# CurrentMonitor2.net
KiCad netlist of a schematic drawn in EAGLE
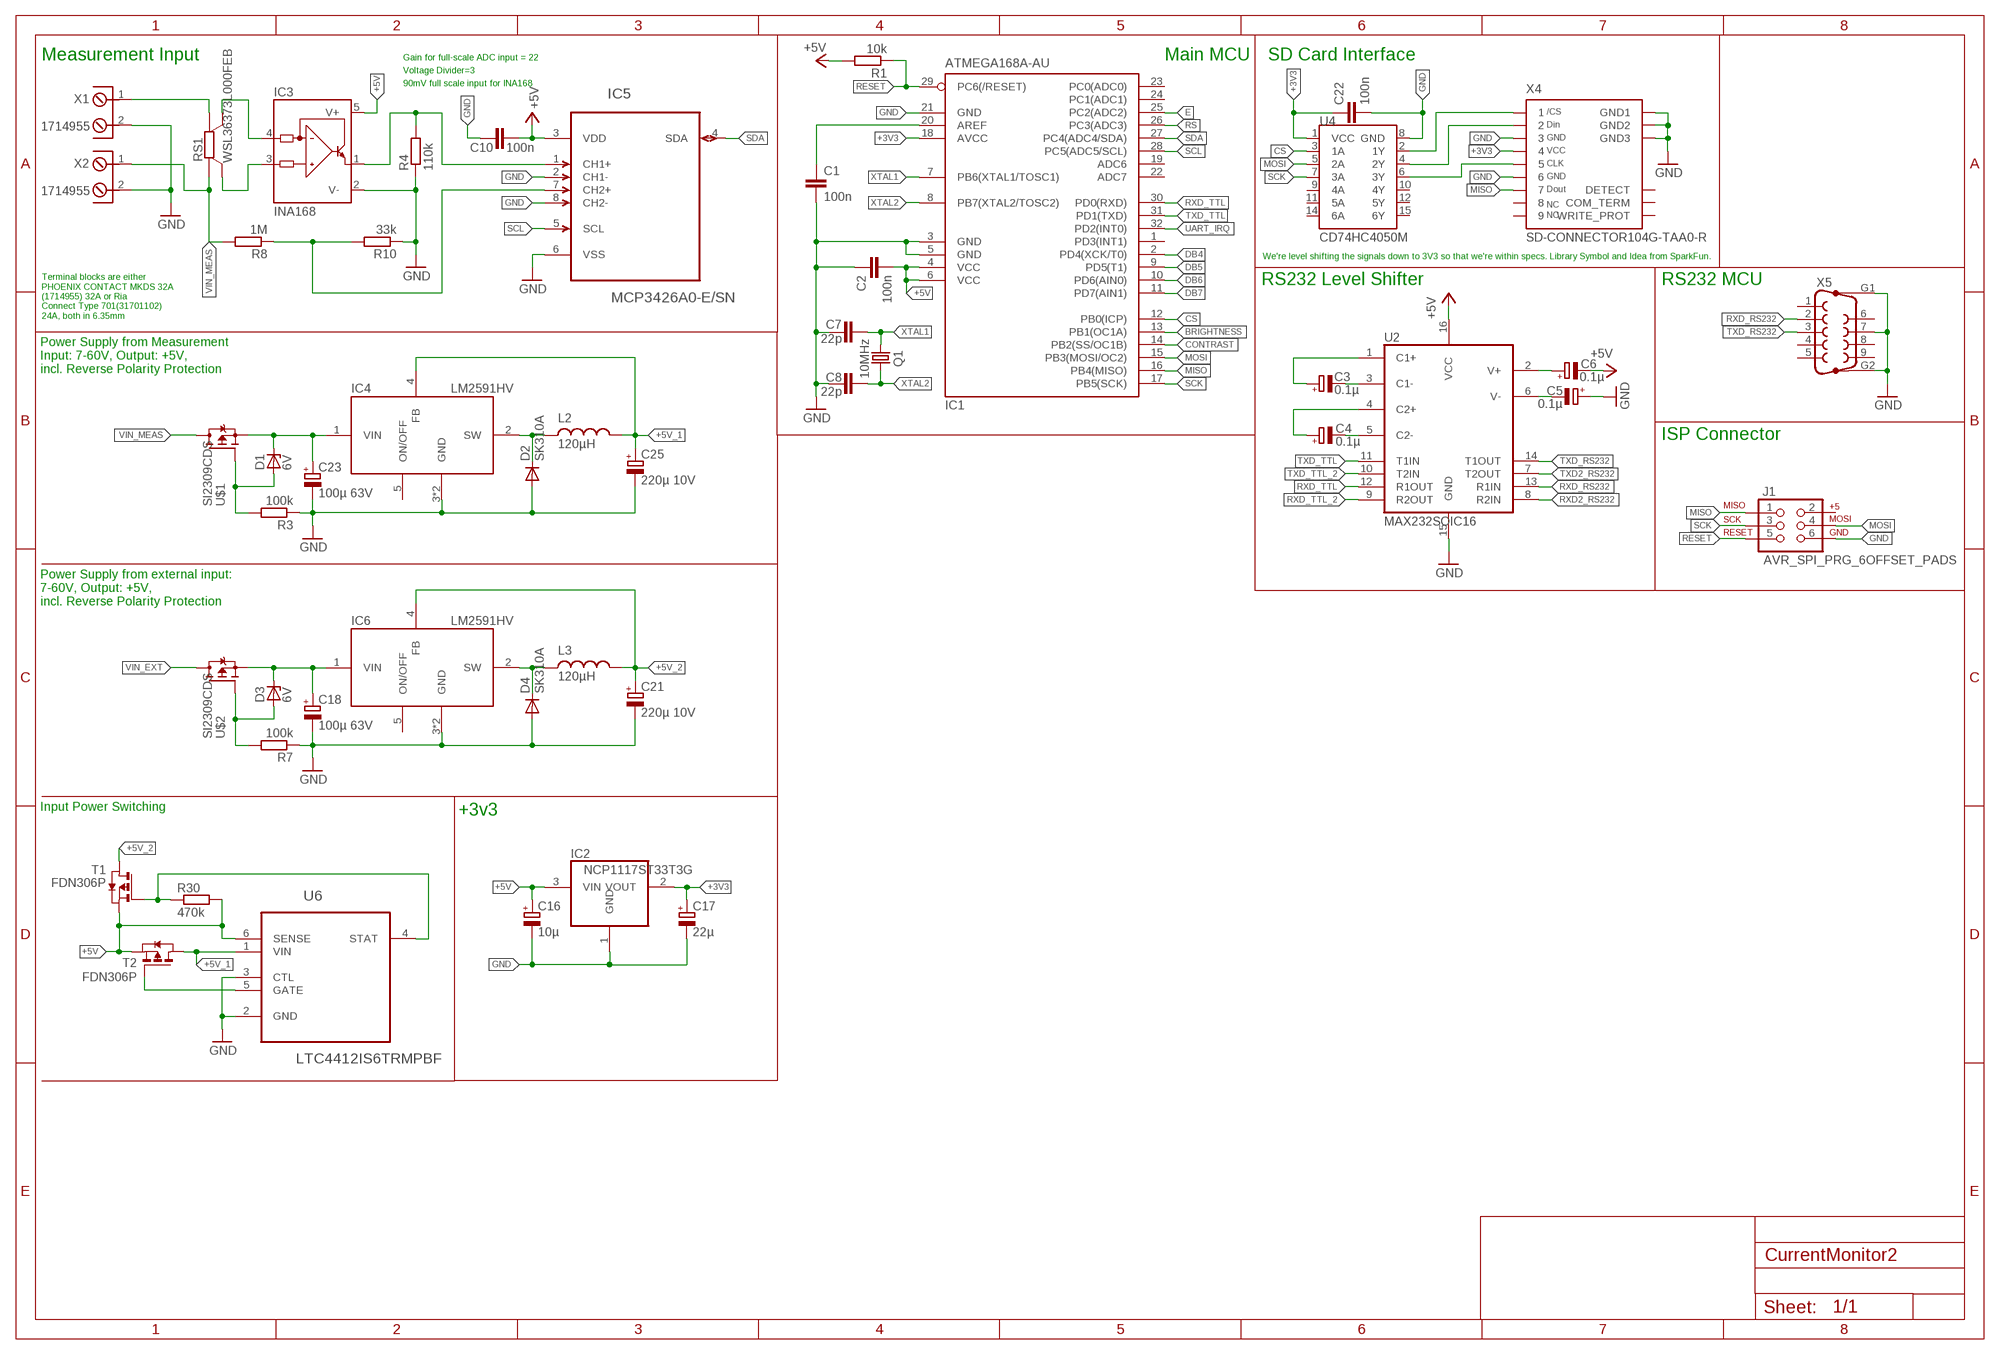
[diagram p0: schematic, sheet 1, part 1 of 2]
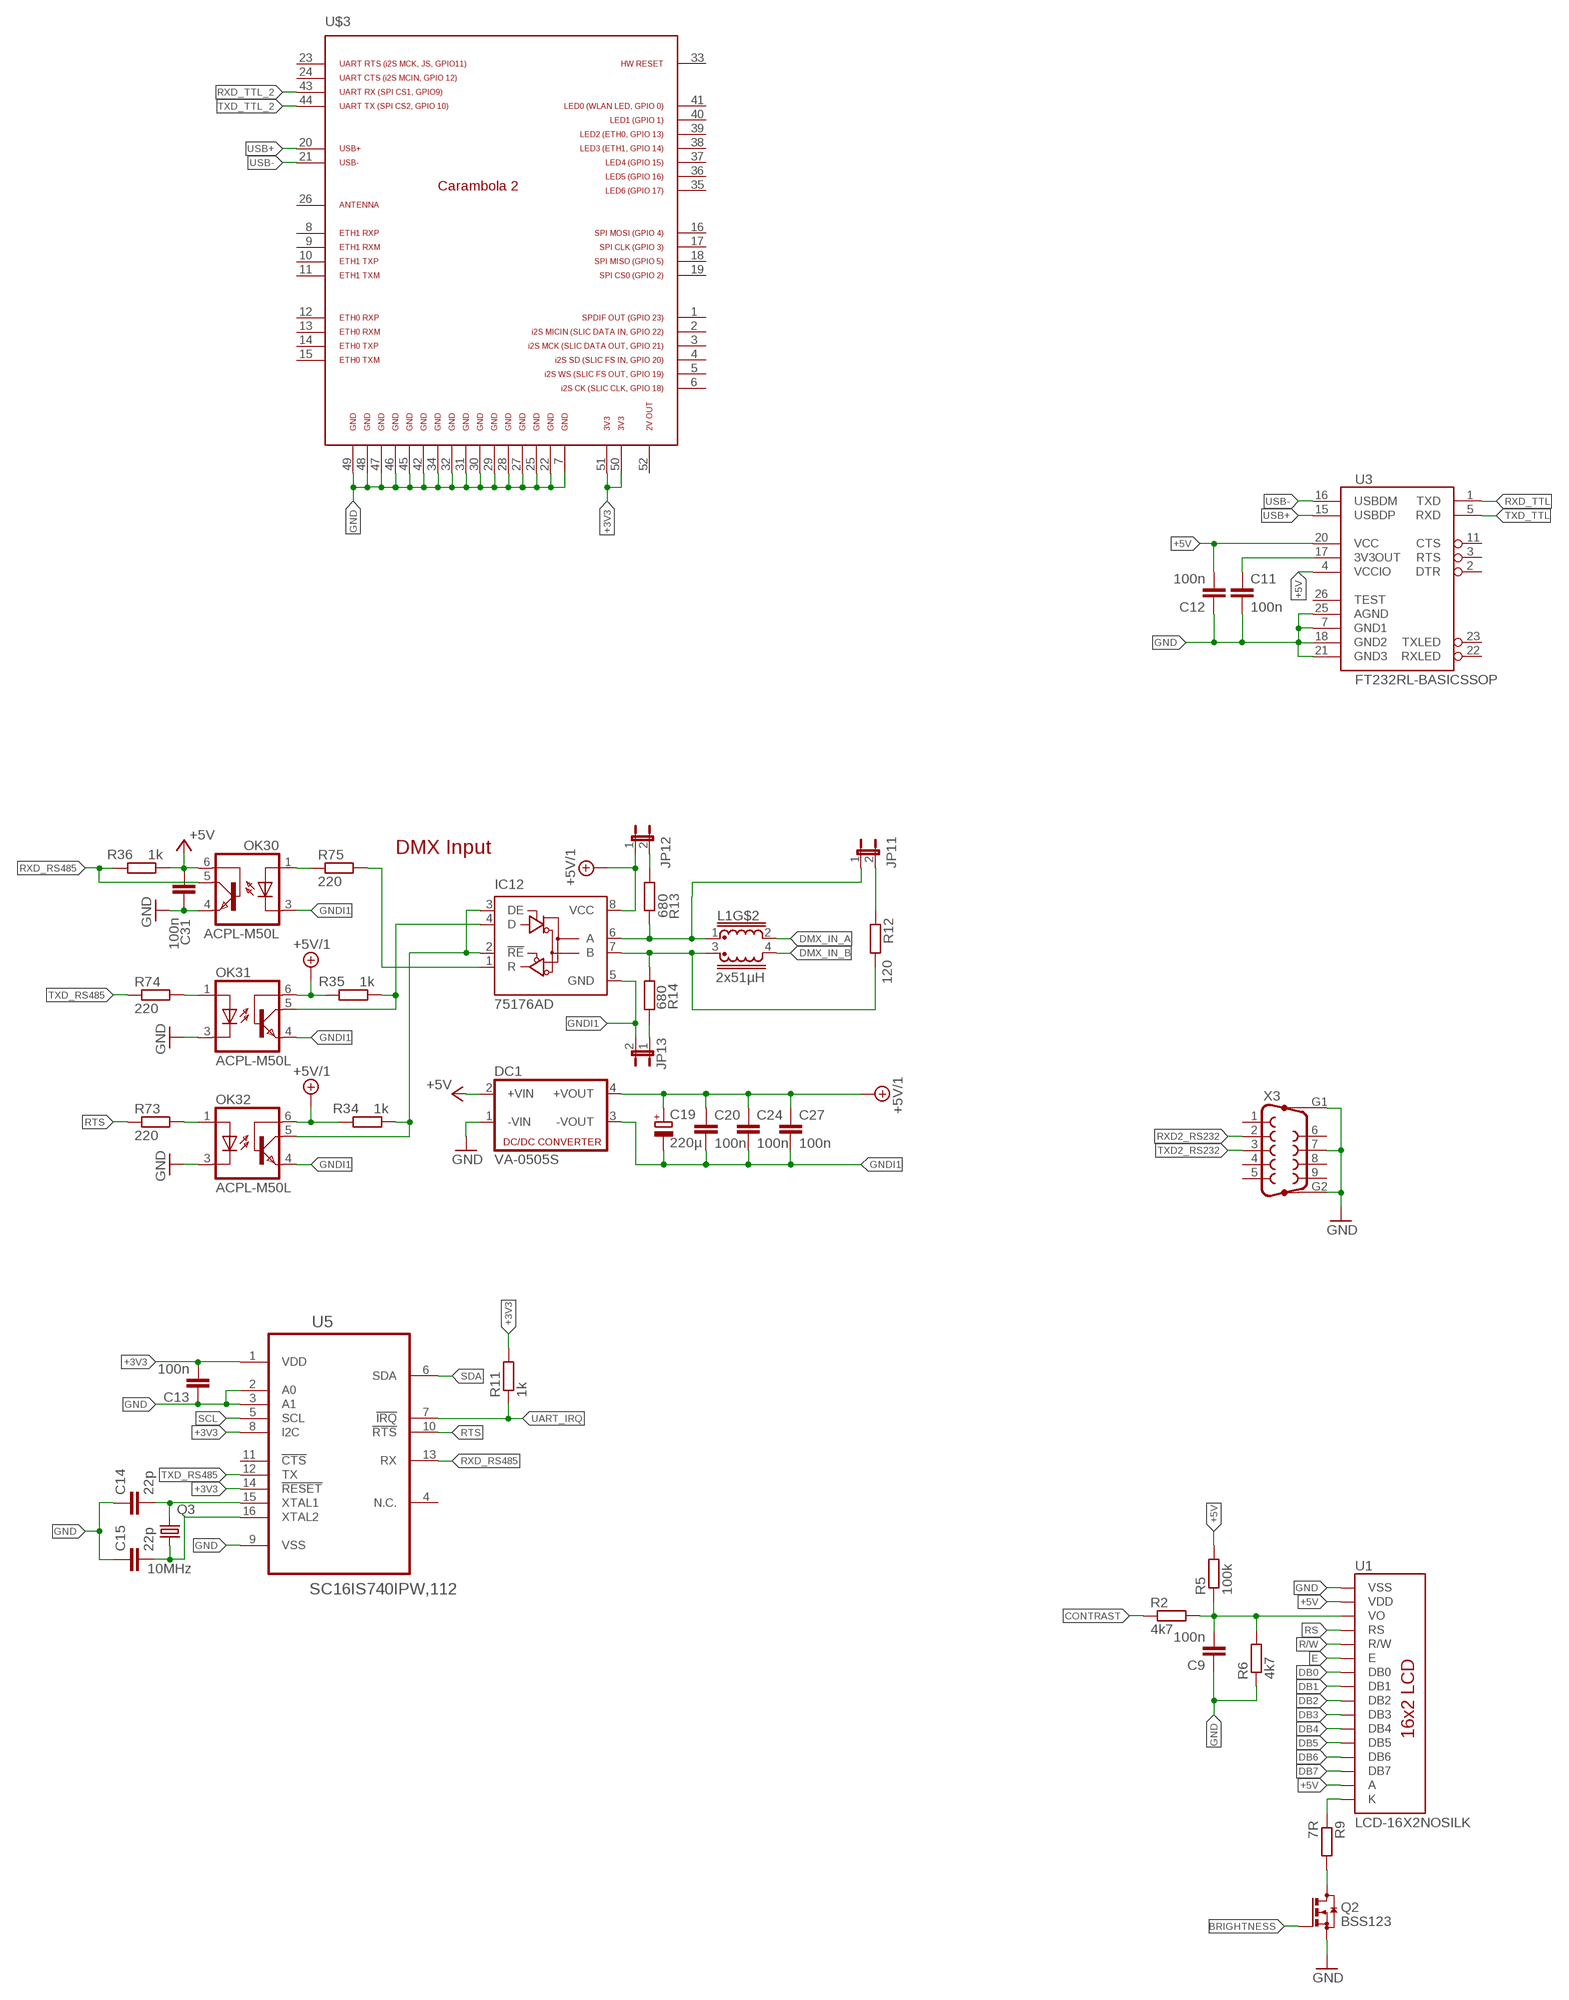
[diagram p1: schematic, sheet 1, part 2 of 2]

(export (version "E")
  (design (tool "Eeschema 10.0.6"))
  (components
    (comp (ref "C1")
      (value "100n")
      (footprint "eagle-import:C0805")
      (libsource (lib "eagle-import") (part "resistor_C-EUC0805"))
    )
    (comp (ref "C2")
      (value "100n")
      (footprint "eagle-import:C0805")
      (libsource (lib "eagle-import") (part "resistor_C-EUC0805"))
    )
    (comp (ref "C3")
      (value "0.1µ")
      (footprint "eagle-import:PANASONIC_B")
      (libsource (lib "eagle-import") (part "CPOL-EUB"))
    )
    (comp (ref "C4")
      (value "0.1µ")
      (footprint "eagle-import:PANASONIC_B")
      (libsource (lib "eagle-import") (part "CPOL-EUB"))
    )
    (comp (ref "C5")
      (value "0.1µ")
      (footprint "eagle-import:PANASONIC_B")
      (libsource (lib "eagle-import") (part "CPOL-EUB"))
    )
    (comp (ref "C6")
      (value "0.1µ")
      (footprint "eagle-import:PANASONIC_B")
      (libsource (lib "eagle-import") (part "CPOL-EUB"))
    )
    (comp (ref "C7")
      (value "22p")
      (footprint "eagle-import:C0805")
      (libsource (lib "eagle-import") (part "C-EUC0805"))
    )
    (comp (ref "C8")
      (value "22p")
      (footprint "eagle-import:C0805")
      (libsource (lib "eagle-import") (part "C-EUC0805"))
    )
    (comp (ref "C9")
      (value "100n")
      (footprint "eagle-import:C0805")
      (libsource (lib "eagle-import") (part "resistor_C-EUC0805"))
    )
    (comp (ref "C10")
      (value "100n")
      (footprint "eagle-import:C0805")
      (libsource (lib "eagle-import") (part "resistor_C-EUC0805"))
    )
    (comp (ref "C11")
      (value "100n")
      (footprint "eagle-import:C0805")
      (libsource (lib "eagle-import") (part "resistor_C-EUC0805"))
    )
    (comp (ref "C12")
      (value "100n")
      (footprint "eagle-import:C0805")
      (libsource (lib "eagle-import") (part "resistor_C-EUC0805"))
    )
    (comp (ref "C13")
      (value "100n")
      (footprint "eagle-import:C0805")
      (libsource (lib "eagle-import") (part "resistor_C-EUC0805"))
    )
    (comp (ref "C14")
      (value "22p")
      (footprint "eagle-import:C0805")
      (libsource (lib "eagle-import") (part "C-EUC0805"))
    )
    (comp (ref "C15")
      (value "22p")
      (footprint "eagle-import:C0805")
      (libsource (lib "eagle-import") (part "C-EUC0805"))
    )
    (comp (ref "C16")
      (value "10µ")
      (footprint "eagle-import:PANASONIC_B")
      (libsource (lib "eagle-import") (part "CPOL-EUB"))
    )
    (comp (ref "C17")
      (value "22µ")
      (footprint "eagle-import:PANASONIC_B")
      (libsource (lib "eagle-import") (part "CPOL-EUB"))
    )
    (comp (ref "C18")
      (value "100µ 63V")
      (footprint "eagle-import:PANASONIC_G")
      (libsource (lib "eagle-import") (part "CPOL-EUG"))
    )
    (comp (ref "C19")
      (value "220µ")
      (footprint "eagle-import:PANASONIC_D")
      (libsource (lib "eagle-import") (part "CPOL-EUD"))
    )
    (comp (ref "C20")
      (value "100n")
      (footprint "eagle-import:C0805")
      (libsource (lib "eagle-import") (part "C-EUC0805"))
    )
    (comp (ref "C21")
      (value "220µ 10V")
      (footprint "eagle-import:PANASONIC_D")
      (libsource (lib "eagle-import") (part "CPOL-EUD"))
    )
    (comp (ref "C22")
      (value "100n")
      (footprint "eagle-import:C0805")
      (libsource (lib "eagle-import") (part "resistor_C-EUC0805"))
    )
    (comp (ref "C23")
      (value "100µ 63V")
      (footprint "eagle-import:PANASONIC_G")
      (libsource (lib "eagle-import") (part "CPOL-EUG"))
    )
    (comp (ref "C24")
      (value "100n")
      (footprint "eagle-import:C0805")
      (libsource (lib "eagle-import") (part "C-EUC0805"))
    )
    (comp (ref "C25")
      (value "220µ 10V")
      (footprint "eagle-import:PANASONIC_D")
      (libsource (lib "eagle-import") (part "CPOL-EUD"))
    )
    (comp (ref "C27")
      (value "100n")
      (footprint "eagle-import:C0805")
      (libsource (lib "eagle-import") (part "C-EUC0805"))
    )
    (comp (ref "C31")
      (value "100n")
      (footprint "eagle-import:C0805")
      (libsource (lib "eagle-import") (part "C-EUC0805"))
    )
    (comp (ref "D1")
      (value "6V")
      (footprint "eagle-import:SOT23")
      (libsource (lib "eagle-import") (part "ZENER-DIODESOT23"))
    )
    (comp (ref "D2")
      (value "SK310A")
      (footprint "eagle-import:DO214AC")
      (libsource (lib "eagle-import") (part "DIODE-DO214AC"))
    )
    (comp (ref "D3")
      (value "6V")
      (footprint "eagle-import:SOT23")
      (libsource (lib "eagle-import") (part "ZENER-DIODESOT23"))
    )
    (comp (ref "D4")
      (value "SK310A")
      (footprint "eagle-import:DO214AC")
      (libsource (lib "eagle-import") (part "DIODE-DO214AC"))
    )
    (comp (ref "DC1")
      (value "VA-0505S")
      (footprint "eagle-import:4SIL")
      (libsource (lib "eagle-import") (part "VA-?S0505"))
    )
    (comp (ref "IC1")
      (value "ATMEGA168A-AU")
      (footprint "eagle-import:TQFP32-08")
      (fields (field (name "MPN") "ATMEGA8-16AU") (field (name "OC_FARNELL") "1841603"))
      (libsource (lib "eagle-import") (part "MEGA8-AI"))
    )
    (comp (ref "IC2")
      (value "NCP1117ST33T3G")
      (footprint "eagle-import:SOT223")
      (fields (field (name "MPN") "REG1117") (field (name "OC_FARNELL") "1652366RL"))
      (libsource (lib "eagle-import") (part "REG1117"))
    )
    (comp (ref "IC3")
      (value "INA168")
      (footprint "eagle-import:SOT23-5")
      (fields
        (field (name "MF") "TEXAS INSTRUMENTS")
        (field (name "MPN") "INA138NA/250")
        (field (name "OC_FARNELL") "1206907RL")
      )
      (libsource (lib "eagle-import") (part "INA138"))
    )
    (comp (ref "IC4")
      (value "LM2591HV")
      (footprint "eagle-import:TO263-5")
      (libsource (lib "eagle-import") (part "LM2591HV"))
    )
    (comp (ref "IC5")
      (value "MCP3426A0-E/SN")
      (footprint "eagle-import:SOIC127P600X175-8N")
      (libsource (lib "eagle-import") (part "MCP3426A0-E/SN"))
    )
    (comp (ref "IC6")
      (value "LM2591HV")
      (footprint "eagle-import:TO263-5")
      (libsource (lib "eagle-import") (part "LM2591HV"))
    )
    (comp (ref "IC12")
      (value "75176AD")
      (footprint "eagle-import:D_R-PDSO-G8")
      (libsource (lib "eagle-import") (part "75176AD"))
    )
    (comp (ref "J1")
      (value "AVR_SPI_PRG_6OFFSET_PADS")
      (footprint "eagle-import:2X3_OFFSET")
      (libsource (lib "eagle-import") (part "AVR_SPI_PRG_6OFFSET_PADS"))
    )
    (comp (ref "JP11")
      (value "JP1E")
      (footprint "eagle-import:JP1")
      (libsource (lib "eagle-import") (part "JP1E"))
    )
    (comp (ref "JP12")
      (value "JP1E")
      (footprint "eagle-import:JP1")
      (libsource (lib "eagle-import") (part "JP1E"))
    )
    (comp (ref "JP13")
      (value "JP1E")
      (footprint "eagle-import:JP1")
      (libsource (lib "eagle-import") (part "JP1E"))
    )
    (comp (ref "L1")
      (value "2x51µH")
      (footprint "eagle-import:EPCOS_B82790_SERIES")
      (libsource (lib "eagle-import") (part "EPCOS_B82790C0"))
    )
    (comp (ref "L2")
      (value "120µH")
      (footprint "eagle-import:MSS1260")
      (libsource (lib "eagle-import") (part "MSS1260"))
    )
    (comp (ref "L3")
      (value "120µH")
      (footprint "eagle-import:MSS1260")
      (libsource (lib "eagle-import") (part "MSS1260"))
    )
    (comp (ref "OK30")
      (value "ACPL-M50L")
      (footprint "eagle-import:JEDEC_MS-012-AA_SOIC5")
      (libsource (lib "eagle-import") (part "ACPL-M50L"))
    )
    (comp (ref "OK31")
      (value "ACPL-M50L")
      (footprint "eagle-import:JEDEC_MS-012-AA_SOIC5")
      (libsource (lib "eagle-import") (part "ACPL-M50L"))
    )
    (comp (ref "OK32")
      (value "ACPL-M50L")
      (footprint "eagle-import:JEDEC_MS-012-AA_SOIC5")
      (libsource (lib "eagle-import") (part "ACPL-M50L"))
    )
    (comp (ref "Q1")
      (value "10MHz")
      (footprint "eagle-import:HC49UP")
      (fields (field (name "OC_FARNELL") "1842273RL"))
      (libsource (lib "eagle-import") (part "CRYSTALHC49UP"))
    )
    (comp (ref "Q2")
      (value "BSS123")
      (footprint "eagle-import:SOT23")
      (libsource (lib "eagle-import") (part "BSS123"))
    )
    (comp (ref "Q3")
      (value "10MHz")
      (footprint "eagle-import:HC49UP")
      (libsource (lib "eagle-import") (part "CRYSTALHC49UP"))
    )
    (comp (ref "R1")
      (value "10k")
      (footprint "eagle-import:R0805")
      (libsource (lib "eagle-import") (part "R-EU_R0805"))
    )
    (comp (ref "R2")
      (value "4k7")
      (footprint "eagle-import:R0805")
      (libsource (lib "eagle-import") (part "R-EU_R0805"))
    )
    (comp (ref "R3")
      (value "100k")
      (footprint "eagle-import:R0805")
      (libsource (lib "eagle-import") (part "R-EU_R0805"))
    )
    (comp (ref "R4")
      (value "110k")
      (footprint "eagle-import:R0805")
      (libsource (lib "eagle-import") (part "R-EU_R0805"))
    )
    (comp (ref "R5")
      (value "100k")
      (footprint "eagle-import:R0805")
      (libsource (lib "eagle-import") (part "R-EU_R0805"))
    )
    (comp (ref "R6")
      (value "4k7")
      (footprint "eagle-import:R0805")
      (libsource (lib "eagle-import") (part "R-EU_R0805"))
    )
    (comp (ref "R7")
      (value "100k")
      (footprint "eagle-import:R0805")
      (libsource (lib "eagle-import") (part "R-EU_R0805"))
    )
    (comp (ref "R8")
      (value "1M")
      (footprint "eagle-import:R0805")
      (libsource (lib "eagle-import") (part "R-EU_R0805"))
    )
    (comp (ref "R9")
      (value "7R")
      (footprint "eagle-import:R0805")
      (libsource (lib "eagle-import") (part "R-EU_R0805"))
    )
    (comp (ref "R10")
      (value "33k")
      (footprint "eagle-import:R0805")
      (libsource (lib "eagle-import") (part "R-EU_R0805"))
    )
    (comp (ref "R11")
      (value "1k")
      (footprint "eagle-import:R0805")
      (libsource (lib "eagle-import") (part "R-EU_R0805"))
    )
    (comp (ref "R12")
      (value "120")
      (footprint "eagle-import:R0805")
      (libsource (lib "eagle-import") (part "R-EU_R0805"))
    )
    (comp (ref "R13")
      (value "680")
      (footprint "eagle-import:R0805")
      (libsource (lib "eagle-import") (part "R-EU_R0805"))
    )
    (comp (ref "R14")
      (value "680")
      (footprint "eagle-import:R0805")
      (libsource (lib "eagle-import") (part "R-EU_R0805"))
    )
    (comp (ref "R30")
      (value "470k")
      (footprint "eagle-import:R0805")
      (libsource (lib "eagle-import") (part "R-EU_R0805"))
    )
    (comp (ref "R34")
      (value "1k")
      (footprint "eagle-import:R0805")
      (libsource (lib "eagle-import") (part "resistor_R-EU_R0805"))
    )
    (comp (ref "R35")
      (value "1k")
      (footprint "eagle-import:R0805")
      (libsource (lib "eagle-import") (part "resistor_R-EU_R0805"))
    )
    (comp (ref "R36")
      (value "1k")
      (footprint "eagle-import:R0805")
      (libsource (lib "eagle-import") (part "resistor_R-EU_R0805"))
    )
    (comp (ref "R73")
      (value "220")
      (footprint "eagle-import:R0805")
      (libsource (lib "eagle-import") (part "resistor_R-EU_R0805"))
    )
    (comp (ref "R74")
      (value "220")
      (footprint "eagle-import:R0805")
      (libsource (lib "eagle-import") (part "resistor_R-EU_R0805"))
    )
    (comp (ref "R75")
      (value "220")
      (footprint "eagle-import:R0805")
      (libsource (lib "eagle-import") (part "resistor_R-EU_R0805"))
    )
    (comp (ref "RS1")
      (value "WSL36373L000FEB")
      (footprint "eagle-import:CSM3637M")
      (libsource (lib "eagle-import") (part "SHUNT-4CSM3675M"))
    )
    (comp (ref "T1")
      (value "FDN306P")
      (footprint "eagle-import:SOT-23")
      (libsource (lib "eagle-import") (part "PMOSSOT23"))
    )
    (comp (ref "T2")
      (value "FDN306P")
      (footprint "eagle-import:SOT-23")
      (libsource (lib "eagle-import") (part "PMOSSOT23"))
    )
    (comp (ref "U$1")
      (value "SI2309CDS")
      (footprint "eagle-import:SOT23")
      (libsource (lib "eagle-import") (part "SI2309CDS"))
    )
    (comp (ref "U$2")
      (value "SI2309CDS")
      (footprint "eagle-import:SOT23")
      (libsource (lib "eagle-import") (part "SI2309CDS"))
    )
    (comp (ref "U$3")
      (value "CARAMBOLA2")
      (footprint "eagle-import:CARAMBOLA2")
      (libsource (lib "eagle-import") (part "CARAMBOLA2"))
    )
    (comp (ref "U1")
      (value "LCD-16X2NOSILK")
      (footprint "eagle-import:LCD-16X2_NOSILK")
      (libsource (lib "eagle-import") (part "LCD-16X2NOSILK"))
    )
    (comp (ref "U2")
      (value "MAX232SOIC16")
      (footprint "eagle-import:SO016")
      (libsource (lib "eagle-import") (part "MAX232SOIC16"))
    )
    (comp (ref "U3")
      (value "FT232RL-BASICSSOP")
      (footprint "eagle-import:SSOP28DB")
      (libsource (lib "eagle-import") (part "FT232RL-BASICSSOP"))
    )
    (comp (ref "U4")
      (value "CD74HC4050M")
      (footprint "eagle-import:SO016")
      (libsource (lib "eagle-import") (part "HEX_CONVERTER"))
    )
    (comp (ref "U5")
      (value "SC16IS740IPW,112")
      (footprint "eagle-import:SOP65P640X110-16N")
      (libsource (lib "eagle-import") (part "SC16IS740IPW,112"))
    )
    (comp (ref "U6")
      (value "LTC4412IS6TRMPBF")
      (footprint "eagle-import:SOT95P280X100-6N")
      (fields (field (name "MPN") "LTC4412IS6#TRMPBF"))
      (libsource (lib "eagle-import") (part "LTC4412IS6TRMPBF"))
    )
    (comp (ref "X1")
      (value "1714955")
      (footprint "eagle-import:AKL701_2_13")
      (libsource (lib "eagle-import") (part "AKL701_213"))
    )
    (comp (ref "X2")
      (value "1714955")
      (footprint "eagle-import:AKL701_2_13")
      (libsource (lib "eagle-import") (part "AKL701_213"))
    )
    (comp (ref "X3")
      (value "F09HP")
      (footprint "eagle-import:F09HP")
      (libsource (lib "eagle-import") (part "F09HP"))
    )
    (comp (ref "X4")
      (value "SD-CONNECTOR104G-TAA0-R")
      (footprint "eagle-import:104G-TAA0-R")
      (libsource (lib "eagle-import") (part "SD-CONNECTOR104G-TAA0-R"))
    )
    (comp (ref "X5")
      (value "F09HP")
      (footprint "eagle-import:F09HP")
      (fields (field (name "OC_FARNELL") "1653978"))
      (libsource (lib "eagle-import") (part "F09HP"))
    )
  )
  (nets
    (net (code "1") (name "+3V3") (class "Default")
      (node (ref "C1") (pin "1") (pinfunction "1_1") (pintype "passive"))
      (node (ref "C13") (pin "2") (pinfunction "2_2") (pintype "passive"))
      (node (ref "C17") (pin "+") (pinfunction "+_+") (pintype "passive"))
      (node (ref "C22") (pin "1") (pinfunction "1_1") (pintype "passive"))
      (node (ref "IC1") (pin "18") (pinfunction "AVCC_18") (pintype "power_in"))
      (node (ref "IC1") (pin "20") (pinfunction "AREF_20") (pintype "passive"))
      (node (ref "IC2") (pin "2") (pinfunction "VOUT_2") (pintype "output"))
      (node (ref "R11") (pin "2") (pinfunction "2_2") (pintype "passive"))
      (node (ref "U$3") (pin "50") (pinfunction "50_50") (pintype "power_in"))
      (node (ref "U$3") (pin "51") (pinfunction "51_51") (pintype "power_in"))
      (node (ref "U4") (pin "1") (pinfunction "VCC_1") (pintype "bidirectional"))
      (node (ref "U5") (pin "1") (pinfunction "VDD_1") (pintype "power_in"))
      (node (ref "U5") (pin "14") (pinfunction "~{RESET}_14") (pintype "input"))
      (node (ref "U5") (pin "8") (pinfunction "I2C_8") (pintype "input"))
      (node (ref "X4") (pin "4") (pinfunction "4_4") (pintype "input"))
    )
    (net (code "2") (name "+5V") (class "Default")
      (node (ref "C10") (pin "1") (pinfunction "1_1") (pintype "passive"))
      (node (ref "C12") (pin "2") (pinfunction "2_2") (pintype "passive"))
      (node (ref "C16") (pin "+") (pinfunction "+_+") (pintype "passive"))
      (node (ref "C2") (pin "2") (pinfunction "2_2") (pintype "passive"))
      (node (ref "C31") (pin "1") (pinfunction "1_1") (pintype "passive"))
      (node (ref "C6") (pin "-") (pinfunction "-_-") (pintype "passive"))
      (node (ref "DC1") (pin "2") (pinfunction "+VIN_2") (pintype "passive"))
      (node (ref "IC1") (pin "4") (pinfunction "VCC_4") (pintype "power_in"))
      (node (ref "IC1") (pin "6") (pinfunction "VCC_6") (pintype "power_in"))
      (node (ref "IC2") (pin "3") (pinfunction "VIN_3") (pintype "input"))
      (node (ref "IC3") (pin "5") (pinfunction "V+_5") (pintype "power_in"))
      (node (ref "IC5") (pin "3") (pinfunction "VDD_3") (pintype "power_in"))
      (node (ref "OK30") (pin "6") (pinfunction "BAS_6") (pintype "passive"))
      (node (ref "R1") (pin "2") (pinfunction "2_2") (pintype "passive"))
      (node (ref "R30") (pin "2") (pinfunction "2_2") (pintype "passive"))
      (node (ref "R36") (pin "1") (pinfunction "1_1") (pintype "passive"))
      (node (ref "R5") (pin "2") (pinfunction "2_2") (pintype "passive"))
      (node (ref "T1") (pin "2") (pinfunction "S_2") (pintype "passive"))
      (node (ref "T2") (pin "2") (pinfunction "S_2") (pintype "passive"))
      (node (ref "U1") (pin "15") (pinfunction "A_15") (pintype "power_in"))
      (node (ref "U1") (pin "2") (pinfunction "VDD_2") (pintype "power_in"))
      (node (ref "U2") (pin "16") (pinfunction "VCC_16") (pintype "bidirectional"))
      (node (ref "U3") (pin "20") (pinfunction "VCC_20") (pintype "power_in"))
      (node (ref "U3") (pin "4") (pinfunction "VCCIO_4") (pintype "power_in"))
      (node (ref "U6") (pin "6") (pinfunction "SENSE_6") (pintype "input"))
    )
    (net (code "3") (name "+5V_1") (class "Default")
      (node (ref "C25") (pin "+") (pinfunction "+_+") (pintype "passive"))
      (node (ref "IC4") (pin "4") (pinfunction "FB_4") (pintype "bidirectional"))
      (node (ref "L2") (pin "P$1") (pinfunction "P$1_P$1") (pintype "passive"))
      (node (ref "T2") (pin "1") (pinfunction "D_1") (pintype "passive"))
      (node (ref "U6") (pin "1") (pinfunction "VIN_1") (pintype "input"))
    )
    (net (code "4") (name "+5V_2") (class "Default")
      (node (ref "C21") (pin "+") (pinfunction "+_+") (pintype "passive"))
      (node (ref "IC6") (pin "4") (pinfunction "FB_4") (pintype "bidirectional"))
      (node (ref "L3") (pin "P$1") (pinfunction "P$1_P$1") (pintype "passive"))
      (node (ref "T1") (pin "1") (pinfunction "D_1") (pintype "passive"))
    )
    (net (code "5") (name "+5V{slash}1") (class "Default")
      (node (ref "C19") (pin "+") (pinfunction "+_+") (pintype "passive"))
      (node (ref "C20") (pin "1") (pinfunction "1_1") (pintype "passive"))
      (node (ref "C24") (pin "1") (pinfunction "1_1") (pintype "passive"))
      (node (ref "C27") (pin "1") (pinfunction "1_1") (pintype "passive"))
      (node (ref "DC1") (pin "4") (pinfunction "+VOUT_4") (pintype "passive"))
      (node (ref "IC12") (pin "8") (pinfunction "VCC_8") (pintype "power_in"))
      (node (ref "JP12") (pin "1") (pinfunction "1_1") (pintype "passive"))
      (node (ref "OK31") (pin "6") (pinfunction "BAS_6") (pintype "passive"))
      (node (ref "OK32") (pin "6") (pinfunction "BAS_6") (pintype "passive"))
      (node (ref "R34") (pin "2") (pinfunction "2_2") (pintype "passive"))
      (node (ref "R35") (pin "2") (pinfunction "2_2") (pintype "passive"))
    )
    (net (code "6") (name "/P$1") (class "Default")
      (node (ref "U$3") (pin "52") (pinfunction "P$1_52") (pintype "power_in"))
    )
    (net (code "7") (name "BRIGHTNESS") (class "Default")
      (node (ref "IC1") (pin "13") (pinfunction "PB1(OC1A)_13") (pintype "bidirectional"))
      (node (ref "Q2") (pin "1") (pinfunction "G_1") (pintype "passive"))
    )
    (net (code "8") (name "CONTRAST") (class "Default")
      (node (ref "IC1") (pin "14") (pinfunction "PB2(SS/OC1B)_14") (pintype "bidirectional"))
      (node (ref "R2") (pin "1") (pinfunction "1_1") (pintype "passive"))
    )
    (net (code "9") (name "CS") (class "Default")
      (node (ref "IC1") (pin "12") (pinfunction "PB0(ICP)_12") (pintype "bidirectional"))
      (node (ref "U4") (pin "3") (pinfunction "1A_3") (pintype "bidirectional"))
    )
    (net (code "10") (name "DB0") (class "Default")
      (node (ref "U1") (pin "7") (pinfunction "DB0_7") (pintype "bidirectional"))
    )
    (net (code "11") (name "DB1") (class "Default")
      (node (ref "U1") (pin "8") (pinfunction "DB1_8") (pintype "bidirectional"))
    )
    (net (code "12") (name "DB2") (class "Default")
      (node (ref "U1") (pin "9") (pinfunction "DB2_9") (pintype "bidirectional"))
    )
    (net (code "13") (name "DB3") (class "Default")
      (node (ref "U1") (pin "10") (pinfunction "DB3_10") (pintype "bidirectional"))
    )
    (net (code "14") (name "DB4") (class "Default")
      (node (ref "IC1") (pin "2") (pinfunction "PD4(XCK/T0)_2") (pintype "bidirectional"))
      (node (ref "U1") (pin "11") (pinfunction "DB4_11") (pintype "bidirectional"))
    )
    (net (code "15") (name "DB5") (class "Default")
      (node (ref "IC1") (pin "9") (pinfunction "PD5(T1)_9") (pintype "bidirectional"))
      (node (ref "U1") (pin "12") (pinfunction "DB5_12") (pintype "bidirectional"))
    )
    (net (code "16") (name "DB6") (class "Default")
      (node (ref "IC1") (pin "10") (pinfunction "PD6(AIN0)_10") (pintype "bidirectional"))
      (node (ref "U1") (pin "13") (pinfunction "DB6_13") (pintype "bidirectional"))
    )
    (net (code "17") (name "DB7") (class "Default")
      (node (ref "IC1") (pin "11") (pinfunction "PD7(AIN1)_11") (pintype "bidirectional"))
      (node (ref "U1") (pin "14") (pinfunction "DB7_14") (pintype "bidirectional"))
    )
    (net (code "18") (name "DMX_IN_A") (class "Default")
      (node (ref "L1") (pin "2") (pinfunction "4_2") (pintype "passive"))
    )
    (net (code "19") (name "DMX_IN_B") (class "Default")
      (node (ref "L1") (pin "4") (pinfunction "4_4") (pintype "passive"))
    )
    (net (code "20") (name "E") (class "Default")
      (node (ref "IC1") (pin "25") (pinfunction "PC2(ADC2)_25") (pintype "bidirectional"))
      (node (ref "U1") (pin "6") (pinfunction "E_6") (pintype "input"))
    )
    (net (code "21") (name "GND") (class "Default")
      (node (ref "C1") (pin "2") (pinfunction "2_2") (pintype "passive"))
      (node (ref "C10") (pin "2") (pinfunction "2_2") (pintype "passive"))
      (node (ref "C11") (pin "2") (pinfunction "2_2") (pintype "passive"))
      (node (ref "C12") (pin "1") (pinfunction "1_1") (pintype "passive"))
      (node (ref "C13") (pin "1") (pinfunction "1_1") (pintype "passive"))
      (node (ref "C14") (pin "1") (pinfunction "1_1") (pintype "passive"))
      (node (ref "C15") (pin "1") (pinfunction "1_1") (pintype "passive"))
      (node (ref "C16") (pin "-") (pinfunction "-_-") (pintype "passive"))
      (node (ref "C17") (pin "-") (pinfunction "-_-") (pintype "passive"))
      (node (ref "C18") (pin "-") (pinfunction "-_-") (pintype "passive"))
      (node (ref "C2") (pin "1") (pinfunction "1_1") (pintype "passive"))
      (node (ref "C21") (pin "-") (pinfunction "-_-") (pintype "passive"))
      (node (ref "C22") (pin "2") (pinfunction "2_2") (pintype "passive"))
      (node (ref "C23") (pin "-") (pinfunction "-_-") (pintype "passive"))
      (node (ref "C25") (pin "-") (pinfunction "-_-") (pintype "passive"))
      (node (ref "C31") (pin "2") (pinfunction "2_2") (pintype "passive"))
      (node (ref "C5") (pin "+") (pinfunction "+_+") (pintype "passive"))
      (node (ref "C7") (pin "1") (pinfunction "1_1") (pintype "passive"))
      (node (ref "C8") (pin "1") (pinfunction "1_1") (pintype "passive"))
      (node (ref "C9") (pin "1") (pinfunction "1_1") (pintype "passive"))
      (node (ref "D2") (pin "A") (pinfunction "A_A") (pintype "passive"))
      (node (ref "D4") (pin "A") (pinfunction "A_A") (pintype "passive"))
      (node (ref "DC1") (pin "1") (pinfunction "-VIN_1") (pintype "passive"))
      (node (ref "IC1") (pin "21") (pinfunction "GND_21") (pintype "power_in"))
      (node (ref "IC1") (pin "3") (pinfunction "GND_3") (pintype "power_in"))
      (node (ref "IC1") (pin "5") (pinfunction "GND_5") (pintype "power_in"))
      (node (ref "IC2") (pin "1") (pinfunction "GND_1") (pintype "power_in"))
      (node (ref "IC3") (pin "2") (pinfunction "V-_2") (pintype "power_in"))
      (node (ref "IC4") (pin "3") (pinfunction "GND_3") (pintype "bidirectional"))
      (node (ref "IC4") (pin "6") (pinfunction "GND_6") (pintype "bidirectional"))
      (node (ref "IC5") (pin "2") (pinfunction "CH1-_2") (pintype "input"))
      (node (ref "IC5") (pin "6") (pinfunction "VSS_6") (pintype "power_in"))
      (node (ref "IC5") (pin "8") (pinfunction "CH2-_8") (pintype "input"))
      (node (ref "IC6") (pin "3") (pinfunction "GND_3") (pintype "bidirectional"))
      (node (ref "IC6") (pin "6") (pinfunction "GND_6") (pintype "bidirectional"))
      (node (ref "J1") (pin "6") (pinfunction "6_6") (pintype "passive"))
      (node (ref "OK30") (pin "4") (pinfunction "EMI_4") (pintype "passive"))
      (node (ref "OK31") (pin "3") (pinfunction "C_3") (pintype "passive"))
      (node (ref "OK32") (pin "3") (pinfunction "C_3") (pintype "passive"))
      (node (ref "Q2") (pin "2") (pinfunction "S_2") (pintype "passive"))
      (node (ref "R10") (pin "1") (pinfunction "1_1") (pintype "passive"))
      (node (ref "R3") (pin "1") (pinfunction "1_1") (pintype "passive"))
      (node (ref "R4") (pin "1") (pinfunction "1_1") (pintype "passive"))
      (node (ref "R6") (pin "1") (pinfunction "1_1") (pintype "passive"))
      (node (ref "R7") (pin "1") (pinfunction "1_1") (pintype "passive"))
      (node (ref "U$3") (pin "22") (pinfunction "22_22") (pintype "power_in"))
      (node (ref "U$3") (pin "25") (pinfunction "25_25") (pintype "power_in"))
      (node (ref "U$3") (pin "27") (pinfunction "27_27") (pintype "power_in"))
      (node (ref "U$3") (pin "28") (pinfunction "28_28") (pintype "power_in"))
      (node (ref "U$3") (pin "29") (pinfunction "29_29") (pintype "power_in"))
      (node (ref "U$3") (pin "30") (pinfunction "30_30") (pintype "power_in"))
      (node (ref "U$3") (pin "31") (pinfunction "31_31") (pintype "power_in"))
      (node (ref "U$3") (pin "32") (pinfunction "32_32") (pintype "power_in"))
      (node (ref "U$3") (pin "34") (pinfunction "34_34") (pintype "power_in"))
      (node (ref "U$3") (pin "42") (pinfunction "42_42") (pintype "power_in"))
      (node (ref "U$3") (pin "45") (pinfunction "45_45") (pintype "power_in"))
      (node (ref "U$3") (pin "46") (pinfunction "46_46") (pintype "power_in"))
      (node (ref "U$3") (pin "47") (pinfunction "47_47") (pintype "power_in"))
      (node (ref "U$3") (pin "48") (pinfunction "48_48") (pintype "power_in"))
      (node (ref "U$3") (pin "49") (pinfunction "49_49") (pintype "power_in"))
      (node (ref "U$3") (pin "7") (pinfunction "7_7") (pintype "power_in"))
      (node (ref "U1") (pin "1") (pinfunction "VSS_1") (pintype "power_in"))
      (node (ref "U2") (pin "15") (pinfunction "GND_15") (pintype "bidirectional"))
      (node (ref "U3") (pin "18") (pinfunction "GND2_18") (pintype "power_in"))
      (node (ref "U3") (pin "21") (pinfunction "GND3_21") (pintype "power_in"))
      (node (ref "U3") (pin "25") (pinfunction "AGND_25") (pintype "power_in"))
      (node (ref "U3") (pin "7") (pinfunction "GND1_7") (pintype "power_in"))
      (node (ref "U4") (pin "8") (pinfunction "GND_8") (pintype "bidirectional"))
      (node (ref "U5") (pin "2") (pinfunction "A0_2") (pintype "input"))
      (node (ref "U5") (pin "3") (pinfunction "A1_3") (pintype "input"))
      (node (ref "U5") (pin "9") (pinfunction "VSS_9") (pintype "power_in"))
      (node (ref "U6") (pin "2") (pinfunction "GND_2") (pintype "passive"))
      (node (ref "U6") (pin "3") (pinfunction "CTL_3") (pintype "input"))
      (node (ref "X1") (pin "2") (pinfunction "2_2") (pintype "passive"))
      (node (ref "X2") (pin "2") (pinfunction "2_2") (pintype "passive"))
      (node (ref "X3") (pin "7") (pinfunction "7_7") (pintype "passive"))
      (node (ref "X3") (pin "G1") (pinfunction "G1_G1") (pintype "passive"))
      (node (ref "X3") (pin "G2") (pinfunction "G2_G2") (pintype "passive"))
      (node (ref "X4") (pin "3") (pinfunction "3_3") (pintype "input"))
      (node (ref "X4") (pin "6") (pinfunction "6_6") (pintype "input"))
      (node (ref "X4") (pin "GND1") (pinfunction "GND1_GND1") (pintype "input"))
      (node (ref "X4") (pin "GND2") (pinfunction "GND2_GND2") (pintype "input"))
      (node (ref "X4") (pin "GND3") (pinfunction "GND3_GND3") (pintype "input"))
      (node (ref "X5") (pin "7") (pinfunction "7_7") (pintype "passive"))
      (node (ref "X5") (pin "G1") (pinfunction "G1_G1") (pintype "passive"))
      (node (ref "X5") (pin "G2") (pinfunction "G2_G2") (pintype "passive"))
    )
    (net (code "22") (name "GNDI1") (class "Default")
      (node (ref "C19") (pin "-") (pinfunction "-_-") (pintype "passive"))
      (node (ref "C20") (pin "2") (pinfunction "2_2") (pintype "passive"))
      (node (ref "C24") (pin "2") (pinfunction "2_2") (pintype "passive"))
      (node (ref "C27") (pin "2") (pinfunction "2_2") (pintype "passive"))
      (node (ref "DC1") (pin "3") (pinfunction "-VOUT_3") (pintype "passive"))
      (node (ref "IC12") (pin "5") (pinfunction "GND_5") (pintype "power_in"))
      (node (ref "JP13") (pin "2") (pinfunction "2_2") (pintype "passive"))
      (node (ref "OK30") (pin "3") (pinfunction "C_3") (pintype "passive"))
      (node (ref "OK31") (pin "4") (pinfunction "EMI_4") (pintype "passive"))
      (node (ref "OK32") (pin "4") (pinfunction "EMI_4") (pintype "passive"))
    )
    (net (code "23") (name "MISO") (class "Default")
      (node (ref "IC1") (pin "16") (pinfunction "PB4(MISO)_16") (pintype "bidirectional"))
      (node (ref "J1") (pin "1") (pinfunction "1_1") (pintype "passive"))
      (node (ref "X4") (pin "7") (pinfunction "7_7") (pintype "input"))
    )
    (net (code "24") (name "MOSI") (class "Default")
      (node (ref "IC1") (pin "15") (pinfunction "PB3(MOSI/OC2)_15") (pintype "bidirectional"))
      (node (ref "J1") (pin "4") (pinfunction "4_4") (pintype "passive"))
      (node (ref "U4") (pin "5") (pinfunction "2A_5") (pintype "bidirectional"))
    )
    (net (code "25") (name "Net-(D1-A)") (class "Default")
      (node (ref "D1") (pin "1") (pinfunction "A_1") (pintype "passive"))
      (node (ref "R3") (pin "2") (pinfunction "2_2") (pintype "passive"))
      (node (ref "U$1") (pin "1") (pinfunction "G_1") (pintype "passive"))
    )
    (net (code "26") (name "Net-(D1-C)") (class "Default")
      (node (ref "C23") (pin "+") (pinfunction "+_+") (pintype "passive"))
      (node (ref "D1") (pin "3") (pinfunction "C_3") (pintype "passive"))
      (node (ref "IC4") (pin "1") (pinfunction "VIN_1") (pintype "bidirectional"))
      (node (ref "U$1") (pin "2") (pinfunction "S_2") (pintype "passive"))
    )
    (net (code "27") (name "Net-(D3-A)") (class "Default")
      (node (ref "D3") (pin "1") (pinfunction "A_1") (pintype "passive"))
      (node (ref "R7") (pin "2") (pinfunction "2_2") (pintype "passive"))
      (node (ref "U$2") (pin "1") (pinfunction "G_1") (pintype "passive"))
    )
    (net (code "28") (name "Net-(D3-C)") (class "Default")
      (node (ref "C18") (pin "+") (pinfunction "+_+") (pintype "passive"))
      (node (ref "D3") (pin "3") (pinfunction "C_3") (pintype "passive"))
      (node (ref "IC6") (pin "1") (pinfunction "VIN_1") (pintype "bidirectional"))
      (node (ref "U$2") (pin "2") (pinfunction "S_2") (pintype "passive"))
    )
    (net (code "29") (name "Net-(IC3-IN+)") (class "Default")
      (node (ref "IC3") (pin "3") (pinfunction "IN+_3") (pintype "input"))
      (node (ref "RS1") (pin "S2") (pinfunction "S2_S2") (pintype "passive"))
    )
    (net (code "30") (name "Net-(IC3-IN-)") (class "Default")
      (node (ref "IC3") (pin "4") (pinfunction "IN-_4") (pintype "input"))
      (node (ref "RS1") (pin "S1") (pinfunction "S1_S1") (pintype "passive"))
    )
    (net (code "31") (name "Net-(IC3-OUT)") (class "Default")
      (node (ref "IC3") (pin "1") (pinfunction "OUT_1") (pintype "output"))
      (node (ref "IC5") (pin "1") (pinfunction "CH1+_1") (pintype "input"))
      (node (ref "R4") (pin "2") (pinfunction "2_2") (pintype "passive"))
    )
    (net (code "32") (name "Net-(IC4-SW)") (class "Default")
      (node (ref "D2") (pin "C") (pinfunction "C_C") (pintype "passive"))
      (node (ref "IC4") (pin "2") (pinfunction "SW_2") (pintype "bidirectional"))
      (node (ref "L2") (pin "P$2") (pinfunction "P$2_P$2") (pintype "passive"))
    )
    (net (code "33") (name "Net-(IC5-CH2+)") (class "Default")
      (node (ref "IC5") (pin "7") (pinfunction "CH2+_7") (pintype "input"))
      (node (ref "R10") (pin "2") (pinfunction "2_2") (pintype "passive"))
      (node (ref "R8") (pin "1") (pinfunction "1_1") (pintype "passive"))
    )
    (net (code "34") (name "Net-(IC6-SW)") (class "Default")
      (node (ref "D4") (pin "C") (pinfunction "C_C") (pintype "passive"))
      (node (ref "IC6") (pin "2") (pinfunction "SW_2") (pintype "bidirectional"))
      (node (ref "L3") (pin "P$2") (pinfunction "P$2_P$2") (pintype "passive"))
    )
    (net (code "35") (name "Net-(IC12-A)") (class "Default")
      (node (ref "IC12") (pin "6") (pinfunction "A_6") (pintype "output"))
      (node (ref "JP11") (pin "1") (pinfunction "1_1") (pintype "passive"))
      (node (ref "L1") (pin "1") (pinfunction "1_1") (pintype "passive"))
      (node (ref "R13") (pin "1") (pinfunction "1_1") (pintype "passive"))
    )
    (net (code "36") (name "Net-(IC12-B)") (class "Default")
      (node (ref "IC12") (pin "7") (pinfunction "B_7") (pintype "output"))
      (node (ref "L1") (pin "3") (pinfunction "1_3") (pintype "passive"))
      (node (ref "R12") (pin "2") (pinfunction "2_2") (pintype "passive"))
      (node (ref "R14") (pin "2") (pinfunction "2_2") (pintype "passive"))
    )
    (net (code "37") (name "Net-(IC12-D)") (class "Default")
      (node (ref "IC12") (pin "4") (pinfunction "D_4") (pintype "input"))
      (node (ref "OK31") (pin "5") (pinfunction "COL_5") (pintype "passive"))
      (node (ref "R35") (pin "1") (pinfunction "1_1") (pintype "passive"))
    )
    (net (code "38") (name "Net-(IC12-DE)") (class "Default")
      (node (ref "IC12") (pin "2") (pinfunction "~{RE}_2") (pintype "input"))
      (node (ref "IC12") (pin "3") (pinfunction "DE_3") (pintype "input"))
      (node (ref "OK32") (pin "5") (pinfunction "COL_5") (pintype "passive"))
      (node (ref "R34") (pin "1") (pinfunction "1_1") (pintype "passive"))
    )
    (net (code "39") (name "Net-(IC12-R)") (class "Default")
      (node (ref "IC12") (pin "1") (pinfunction "R_1") (pintype "input"))
      (node (ref "R75") (pin "2") (pinfunction "2_2") (pintype "passive"))
    )
    (net (code "40") (name "Net-(JP11-Pad2)") (class "Default")
      (node (ref "JP11") (pin "2") (pinfunction "2_2") (pintype "passive"))
      (node (ref "R12") (pin "1") (pinfunction "1_1") (pintype "passive"))
    )
    (net (code "41") (name "Net-(JP12-Pad2)") (class "Default")
      (node (ref "JP12") (pin "2") (pinfunction "2_2") (pintype "passive"))
      (node (ref "R13") (pin "2") (pinfunction "2_2") (pintype "passive"))
    )
    (net (code "42") (name "Net-(JP13-Pad1)") (class "Default")
      (node (ref "JP13") (pin "1") (pinfunction "1_1") (pintype "passive"))
      (node (ref "R14") (pin "1") (pinfunction "1_1") (pintype "passive"))
    )
    (net (code "43") (name "Net-(OK30-A)") (class "Default")
      (node (ref "OK30") (pin "1") (pinfunction "A_1") (pintype "passive"))
      (node (ref "R75") (pin "1") (pinfunction "1_1") (pintype "passive"))
    )
    (net (code "44") (name "Net-(OK31-A)") (class "Default")
      (node (ref "OK31") (pin "1") (pinfunction "A_1") (pintype "passive"))
      (node (ref "R74") (pin "2") (pinfunction "2_2") (pintype "passive"))
    )
    (net (code "45") (name "Net-(OK32-A)") (class "Default")
      (node (ref "OK32") (pin "1") (pinfunction "A_1") (pintype "passive"))
      (node (ref "R73") (pin "2") (pinfunction "2_2") (pintype "passive"))
    )
    (net (code "46") (name "Net-(Q2-D)") (class "Default")
      (node (ref "Q2") (pin "3") (pinfunction "D_3") (pintype "passive"))
      (node (ref "R9") (pin "2") (pinfunction "2_2") (pintype "passive"))
    )
    (net (code "47") (name "Net-(RS1-PadI1)") (class "Default")
      (node (ref "RS1") (pin "I1") (pinfunction "I1_I1") (pintype "passive"))
      (node (ref "X1") (pin "1") (pinfunction "1_1") (pintype "passive"))
    )
    (net (code "48") (name "Net-(T1-G)") (class "Default")
      (node (ref "R30") (pin "1") (pinfunction "1_1") (pintype "passive"))
      (node (ref "T1") (pin "3") (pinfunction "G_3") (pintype "passive"))
      (node (ref "U6") (pin "4") (pinfunction "STAT_4") (pintype "output"))
    )
    (net (code "49") (name "Net-(T2-G)") (class "Default")
      (node (ref "T2") (pin "3") (pinfunction "G_3") (pintype "passive"))
      (node (ref "U6") (pin "5") (pinfunction "GATE_5") (pintype "passive"))
    )
    (net (code "50") (name "Net-(U1-K)") (class "Default")
      (node (ref "R9") (pin "1") (pinfunction "1_1") (pintype "passive"))
      (node (ref "U1") (pin "16") (pinfunction "K_16") (pintype "power_in"))
    )
    (net (code "51") (name "Net-(U1-VO)") (class "Default")
      (node (ref "C9") (pin "2") (pinfunction "2_2") (pintype "passive"))
      (node (ref "R2") (pin "2") (pinfunction "2_2") (pintype "passive"))
      (node (ref "R5") (pin "1") (pinfunction "1_1") (pintype "passive"))
      (node (ref "R6") (pin "2") (pinfunction "2_2") (pintype "passive"))
      (node (ref "U1") (pin "3") (pinfunction "VO_3") (pintype "bidirectional"))
    )
    (net (code "52") (name "Net-(U2-C1+)") (class "Default")
      (node (ref "C3") (pin "+") (pinfunction "+_+") (pintype "passive"))
      (node (ref "U2") (pin "1") (pinfunction "C1+_1") (pintype "bidirectional"))
    )
    (net (code "53") (name "Net-(U2-C1-)") (class "Default")
      (node (ref "C3") (pin "-") (pinfunction "-_-") (pintype "passive"))
      (node (ref "U2") (pin "3") (pinfunction "C1-_3") (pintype "bidirectional"))
    )
    (net (code "54") (name "Net-(U2-C2+)") (class "Default")
      (node (ref "C4") (pin "+") (pinfunction "+_+") (pintype "passive"))
      (node (ref "U2") (pin "4") (pinfunction "C2+_4") (pintype "bidirectional"))
    )
    (net (code "55") (name "Net-(U2-C2-)") (class "Default")
      (node (ref "C4") (pin "-") (pinfunction "-_-") (pintype "passive"))
      (node (ref "U2") (pin "5") (pinfunction "C2-_5") (pintype "bidirectional"))
    )
    (net (code "56") (name "Net-(U2-V+)") (class "Default")
      (node (ref "C6") (pin "+") (pinfunction "+_+") (pintype "passive"))
      (node (ref "U2") (pin "2") (pinfunction "V+_2") (pintype "bidirectional"))
    )
    (net (code "57") (name "Net-(U2-V-)") (class "Default")
      (node (ref "C5") (pin "-") (pinfunction "-_-") (pintype "passive"))
      (node (ref "U2") (pin "6") (pinfunction "V-_6") (pintype "bidirectional"))
    )
    (net (code "58") (name "Net-(U3-3V3OUT)") (class "Default")
      (node (ref "C11") (pin "1") (pinfunction "1_1") (pintype "passive"))
      (node (ref "U3") (pin "17") (pinfunction "3V3OUT_17") (pintype "output"))
    )
    (net (code "59") (name "Net-(U4-1Y)") (class "Default")
      (node (ref "U4") (pin "2") (pinfunction "1Y_2") (pintype "bidirectional"))
      (node (ref "X4") (pin "1") (pinfunction "1_1") (pintype "input"))
    )
    (net (code "60") (name "Net-(U4-2Y)") (class "Default")
      (node (ref "U4") (pin "4") (pinfunction "2Y_4") (pintype "bidirectional"))
      (node (ref "X4") (pin "2") (pinfunction "2_2") (pintype "input"))
    )
    (net (code "61") (name "Net-(U4-3Y)") (class "Default")
      (node (ref "U4") (pin "6") (pinfunction "3Y_6") (pintype "bidirectional"))
      (node (ref "X4") (pin "5") (pinfunction "5_5") (pintype "input"))
    )
    (net (code "62") (name "Net-(U5-XTAL1)") (class "Default")
      (node (ref "C14") (pin "2") (pinfunction "2_2") (pintype "passive"))
      (node (ref "Q3") (pin "2") (pinfunction "2_2") (pintype "passive"))
      (node (ref "U5") (pin "15") (pinfunction "XTAL1_15") (pintype "input"))
    )
    (net (code "63") (name "Net-(U5-XTAL2)") (class "Default")
      (node (ref "C15") (pin "2") (pinfunction "2_2") (pintype "passive"))
      (node (ref "Q3") (pin "1") (pinfunction "1_1") (pintype "passive"))
      (node (ref "U5") (pin "16") (pinfunction "XTAL2_16") (pintype "output"))
    )
    (net (code "64") (name "RESET") (class "Default")
      (node (ref "IC1") (pin "29") (pinfunction "PC6(/RESET)_29") (pintype "bidirectional"))
      (node (ref "J1") (pin "5") (pinfunction "5_5") (pintype "passive"))
      (node (ref "R1") (pin "1") (pinfunction "1_1") (pintype "passive"))
    )
    (net (code "65") (name "RS") (class "Default")
      (node (ref "IC1") (pin "26") (pinfunction "PC3(ADC3)_26") (pintype "bidirectional"))
      (node (ref "U1") (pin "4") (pinfunction "RS_4") (pintype "input"))
    )
    (net (code "66") (name "RTS") (class "Default")
      (node (ref "R73") (pin "1") (pinfunction "1_1") (pintype "passive"))
      (node (ref "U5") (pin "10") (pinfunction "~{RTS}_10") (pintype "output"))
    )
    (net (code "67") (name "RXD2_RS232") (class "Default")
      (node (ref "U2") (pin "8") (pinfunction "R2IN_8") (pintype "input"))
      (node (ref "X3") (pin "2") (pinfunction "2_2") (pintype "passive"))
    )
    (net (code "68") (name "RXD_RS232") (class "Default")
      (node (ref "U2") (pin "13") (pinfunction "R1IN_13") (pintype "input"))
      (node (ref "X5") (pin "2") (pinfunction "2_2") (pintype "passive"))
    )
    (net (code "69") (name "RXD_RS485") (class "Default")
      (node (ref "OK30") (pin "5") (pinfunction "COL_5") (pintype "passive"))
      (node (ref "R36") (pin "2") (pinfunction "2_2") (pintype "passive"))
      (node (ref "U5") (pin "13") (pinfunction "RX_13") (pintype "output"))
    )
    (net (code "70") (name "RXD_TTL") (class "Default")
      (node (ref "IC1") (pin "30") (pinfunction "PD0(RXD)_30") (pintype "bidirectional"))
      (node (ref "U2") (pin "12") (pinfunction "R1OUT_12") (pintype "output"))
      (node (ref "U3") (pin "1") (pinfunction "TXD_1") (pintype "output"))
    )
    (net (code "71") (name "RXD_TTL_2") (class "Default")
      (node (ref "U$3") (pin "43") (pinfunction "43_43") (pintype "input"))
      (node (ref "U2") (pin "9") (pinfunction "R2OUT_9") (pintype "output"))
    )
    (net (code "72") (name "R{slash}W") (class "Default")
      (node (ref "U1") (pin "5") (pinfunction "R/W_5") (pintype "input"))
    )
    (net (code "73") (name "SCK") (class "Default")
      (node (ref "IC1") (pin "17") (pinfunction "PB5(SCK)_17") (pintype "bidirectional"))
      (node (ref "J1") (pin "3") (pinfunction "3_3") (pintype "passive"))
      (node (ref "U4") (pin "7") (pinfunction "3A_7") (pintype "bidirectional"))
    )
    (net (code "74") (name "SCL") (class "Default")
      (node (ref "IC1") (pin "28") (pinfunction "PC5(ADC5/SCL)_28") (pintype "bidirectional"))
      (node (ref "IC5") (pin "5") (pinfunction "SCL_5") (pintype "input"))
      (node (ref "U5") (pin "5") (pinfunction "SCL_5") (pintype "input"))
    )
    (net (code "75") (name "SDA") (class "Default")
      (node (ref "IC1") (pin "27") (pinfunction "PC4(ADC4/SDA)_27") (pintype "bidirectional"))
      (node (ref "IC5") (pin "4") (pinfunction "SDA_4") (pintype "bidirectional"))
      (node (ref "U5") (pin "6") (pinfunction "SDA_6") (pintype "bidirectional"))
    )
    (net (code "76") (name "TXD2_RS232") (class "Default")
      (node (ref "U2") (pin "7") (pinfunction "T2OUT_7") (pintype "output"))
      (node (ref "X3") (pin "3") (pinfunction "3_3") (pintype "passive"))
    )
    (net (code "77") (name "TXD_RS232") (class "Default")
      (node (ref "U2") (pin "14") (pinfunction "T1OUT_14") (pintype "output"))
      (node (ref "X5") (pin "3") (pinfunction "3_3") (pintype "passive"))
    )
    (net (code "78") (name "TXD_RS485") (class "Default")
      (node (ref "R74") (pin "1") (pinfunction "1_1") (pintype "passive"))
      (node (ref "U5") (pin "12") (pinfunction "TX_12") (pintype "input"))
    )
    (net (code "79") (name "TXD_TTL") (class "Default")
      (node (ref "IC1") (pin "31") (pinfunction "PD1(TXD)_31") (pintype "bidirectional"))
      (node (ref "U2") (pin "11") (pinfunction "T1IN_11") (pintype "input"))
      (node (ref "U3") (pin "5") (pinfunction "RXD_5") (pintype "input"))
    )
    (net (code "80") (name "TXD_TTL_2") (class "Default")
      (node (ref "U$3") (pin "44") (pinfunction "44_44") (pintype "output"))
      (node (ref "U2") (pin "10") (pinfunction "T2IN_10") (pintype "input"))
    )
    (net (code "81") (name "UART_IRQ") (class "Default")
      (node (ref "IC1") (pin "32") (pinfunction "PD2(INT0)_32") (pintype "bidirectional"))
      (node (ref "R11") (pin "1") (pinfunction "1_1") (pintype "passive"))
      (node (ref "U5") (pin "7") (pinfunction "~{IRQ}_7") (pintype "output"))
    )
    (net (code "82") (name "USB+") (class "Default")
      (node (ref "U$3") (pin "20") (pinfunction "20_20") (pintype "output"))
      (node (ref "U3") (pin "15") (pinfunction "USBDP_15") (pintype "bidirectional"))
    )
    (net (code "83") (name "USB-") (class "Default")
      (node (ref "U$3") (pin "21") (pinfunction "21_21") (pintype "output"))
      (node (ref "U3") (pin "16") (pinfunction "USBDM_16") (pintype "bidirectional"))
    )
    (net (code "84") (name "VIN_EXT") (class "Default")
      (node (ref "U$2") (pin "3") (pinfunction "D_3") (pintype "passive"))
    )
    (net (code "85") (name "VIN_MEAS") (class "Default")
      (node (ref "R8") (pin "2") (pinfunction "2_2") (pintype "passive"))
      (node (ref "RS1") (pin "I2") (pinfunction "I2_I2") (pintype "passive"))
      (node (ref "U$1") (pin "3") (pinfunction "D_3") (pintype "passive"))
      (node (ref "X2") (pin "1") (pinfunction "1_1") (pintype "passive"))
    )
    (net (code "86") (name "XTAL1") (class "Default")
      (node (ref "C7") (pin "2") (pinfunction "2_2") (pintype "passive"))
      (node (ref "IC1") (pin "7") (pinfunction "PB6(XTAL1/TOSC1)_7") (pintype "bidirectional"))
      (node (ref "Q1") (pin "2") (pinfunction "2_2") (pintype "passive"))
    )
    (net (code "87") (name "XTAL2") (class "Default")
      (node (ref "C8") (pin "2") (pinfunction "2_2") (pintype "passive"))
      (node (ref "IC1") (pin "8") (pinfunction "PB7(XTAL2/TOSC2)_8") (pintype "bidirectional"))
      (node (ref "Q1") (pin "1") (pinfunction "1_1") (pintype "passive"))
    )
    (net (code "88") (name "unconnected-(IC1-ADC6-Pad19)") (class "Default")
      (node (ref "IC1") (pin "19") (pinfunction "ADC6_19") (pintype "bidirectional"))
    )
    (net (code "89") (name "unconnected-(IC1-ADC7-Pad22)") (class "Default")
      (node (ref "IC1") (pin "22") (pinfunction "ADC7_22") (pintype "bidirectional"))
    )
    (net (code "90") (name "unconnected-(IC1-PC0(ADC0)-Pad23)") (class "Default")
      (node (ref "IC1") (pin "23") (pinfunction "PC0(ADC0)_23") (pintype "bidirectional"))
    )
    (net (code "91") (name "unconnected-(IC1-PC1(ADC1)-Pad24)") (class "Default")
      (node (ref "IC1") (pin "24") (pinfunction "PC1(ADC1)_24") (pintype "bidirectional"))
    )
    (net (code "92") (name "unconnected-(IC1-PD3(INT1)-Pad1)") (class "Default")
      (node (ref "IC1") (pin "1") (pinfunction "PD3(INT1)_1") (pintype "bidirectional"))
    )
    (net (code "93") (name "unconnected-(IC4-ON{slash}OFF-Pad5)") (class "Default")
      (node (ref "IC4") (pin "5") (pinfunction "ON/OFF_5") (pintype "bidirectional"))
    )
    (net (code "94") (name "unconnected-(IC6-ON{slash}OFF-Pad5)") (class "Default")
      (node (ref "IC6") (pin "5") (pinfunction "ON/OFF_5") (pintype "bidirectional"))
    )
    (net (code "95") (name "unconnected-(J1-Pad2)") (class "Default")
      (node (ref "J1") (pin "2") (pinfunction "2_2") (pintype "passive"))
    )
    (net (code "96") (name "unconnected-(U$3-Pad1)") (class "Default")
      (node (ref "U$3") (pin "1") (pinfunction "1_1") (pintype "bidirectional"))
    )
    (net (code "97") (name "unconnected-(U$3-Pad2)") (class "Default")
      (node (ref "U$3") (pin "2") (pinfunction "2_2") (pintype "bidirectional"))
    )
    (net (code "98") (name "unconnected-(U$3-Pad3)") (class "Default")
      (node (ref "U$3") (pin "3") (pinfunction "3_3") (pintype "bidirectional"))
    )
    (net (code "99") (name "unconnected-(U$3-Pad4)") (class "Default")
      (node (ref "U$3") (pin "4") (pinfunction "4_4") (pintype "bidirectional"))
    )
    (net (code "100") (name "unconnected-(U$3-Pad5)") (class "Default")
      (node (ref "U$3") (pin "5") (pinfunction "5_5") (pintype "bidirectional"))
    )
    (net (code "101") (name "unconnected-(U$3-Pad6)") (class "Default")
      (node (ref "U$3") (pin "6") (pinfunction "6_6") (pintype "bidirectional"))
    )
    (net (code "102") (name "unconnected-(U$3-Pad8)") (class "Default")
      (node (ref "U$3") (pin "8") (pinfunction "8_8") (pintype "input"))
    )
    (net (code "103") (name "unconnected-(U$3-Pad9)") (class "Default")
      (node (ref "U$3") (pin "9") (pinfunction "9_9") (pintype "input"))
    )
    (net (code "104") (name "unconnected-(U$3-Pad10)") (class "Default")
      (node (ref "U$3") (pin "10") (pinfunction "10_10") (pintype "output"))
    )
    (net (code "105") (name "unconnected-(U$3-Pad11)") (class "Default")
      (node (ref "U$3") (pin "11") (pinfunction "11_11") (pintype "output"))
    )
    (net (code "106") (name "unconnected-(U$3-Pad12)") (class "Default")
      (node (ref "U$3") (pin "12") (pinfunction "12_12") (pintype "input"))
    )
    (net (code "107") (name "unconnected-(U$3-Pad13)") (class "Default")
      (node (ref "U$3") (pin "13") (pinfunction "13_13") (pintype "input"))
    )
    (net (code "108") (name "unconnected-(U$3-Pad14)") (class "Default")
      (node (ref "U$3") (pin "14") (pinfunction "14_14") (pintype "output"))
    )
    (net (code "109") (name "unconnected-(U$3-Pad15)") (class "Default")
      (node (ref "U$3") (pin "15") (pinfunction "15_15") (pintype "output"))
    )
    (net (code "110") (name "unconnected-(U$3-Pad16)") (class "Default")
      (node (ref "U$3") (pin "16") (pinfunction "16_16") (pintype "bidirectional"))
    )
    (net (code "111") (name "unconnected-(U$3-Pad17)") (class "Default")
      (node (ref "U$3") (pin "17") (pinfunction "17_17") (pintype "bidirectional"))
    )
    (net (code "112") (name "unconnected-(U$3-Pad18)") (class "Default")
      (node (ref "U$3") (pin "18") (pinfunction "18_18") (pintype "bidirectional"))
    )
    (net (code "113") (name "unconnected-(U$3-Pad19)") (class "Default")
      (node (ref "U$3") (pin "19") (pinfunction "19_19") (pintype "bidirectional"))
    )
    (net (code "114") (name "unconnected-(U$3-Pad23)") (class "Default")
      (node (ref "U$3") (pin "23") (pinfunction "23_23") (pintype "input"))
    )
    (net (code "115") (name "unconnected-(U$3-Pad24)") (class "Default")
      (node (ref "U$3") (pin "24") (pinfunction "24_24") (pintype "input"))
    )
    (net (code "116") (name "unconnected-(U$3-Pad26)") (class "Default")
      (node (ref "U$3") (pin "26") (pinfunction "26_26") (pintype "output"))
    )
    (net (code "117") (name "unconnected-(U$3-Pad33)") (class "Default")
      (node (ref "U$3") (pin "33") (pinfunction "33_33") (pintype "bidirectional"))
    )
    (net (code "118") (name "unconnected-(U$3-Pad35)") (class "Default")
      (node (ref "U$3") (pin "35") (pinfunction "35_35") (pintype "bidirectional"))
    )
    (net (code "119") (name "unconnected-(U$3-Pad36)") (class "Default")
      (node (ref "U$3") (pin "36") (pinfunction "36_36") (pintype "bidirectional"))
    )
    (net (code "120") (name "unconnected-(U$3-Pad37)") (class "Default")
      (node (ref "U$3") (pin "37") (pinfunction "37_37") (pintype "bidirectional"))
    )
    (net (code "121") (name "unconnected-(U$3-Pad38)") (class "Default")
      (node (ref "U$3") (pin "38") (pinfunction "38_38") (pintype "bidirectional"))
    )
    (net (code "122") (name "unconnected-(U$3-Pad39)") (class "Default")
      (node (ref "U$3") (pin "39") (pinfunction "39_39") (pintype "bidirectional"))
    )
    (net (code "123") (name "unconnected-(U$3-Pad40)") (class "Default")
      (node (ref "U$3") (pin "40") (pinfunction "40_40") (pintype "bidirectional"))
    )
    (net (code "124") (name "unconnected-(U$3-Pad41)") (class "Default")
      (node (ref "U$3") (pin "41") (pinfunction "41_41") (pintype "bidirectional"))
    )
    (net (code "125") (name "unconnected-(U3-CTS-Pad11)") (class "Default")
      (node (ref "U3") (pin "11") (pinfunction "CTS_11") (pintype "bidirectional"))
    )
    (net (code "126") (name "unconnected-(U3-DTR-Pad2)") (class "Default")
      (node (ref "U3") (pin "2") (pinfunction "DTR_2") (pintype "bidirectional"))
    )
    (net (code "127") (name "unconnected-(U3-RTS-Pad3)") (class "Default")
      (node (ref "U3") (pin "3") (pinfunction "RTS_3") (pintype "bidirectional"))
    )
    (net (code "128") (name "unconnected-(U3-RXLED-Pad22)") (class "Default")
      (node (ref "U3") (pin "22") (pinfunction "RXLED_22") (pintype "bidirectional"))
    )
    (net (code "129") (name "unconnected-(U3-TEST-Pad26)") (class "Default")
      (node (ref "U3") (pin "26") (pinfunction "TEST_26") (pintype "input"))
    )
    (net (code "130") (name "unconnected-(U3-TXLED-Pad23)") (class "Default")
      (node (ref "U3") (pin "23") (pinfunction "TXLED_23") (pintype "bidirectional"))
    )
    (net (code "131") (name "unconnected-(U4-4A-Pad9)") (class "Default")
      (node (ref "U4") (pin "9") (pinfunction "4A_9") (pintype "bidirectional"))
    )
    (net (code "132") (name "unconnected-(U4-4Y-Pad10)") (class "Default")
      (node (ref "U4") (pin "10") (pinfunction "4Y_10") (pintype "bidirectional"))
    )
    (net (code "133") (name "unconnected-(U4-5A-Pad11)") (class "Default")
      (node (ref "U4") (pin "11") (pinfunction "5A_11") (pintype "bidirectional"))
    )
    (net (code "134") (name "unconnected-(U4-5Y-Pad12)") (class "Default")
      (node (ref "U4") (pin "12") (pinfunction "5Y_12") (pintype "bidirectional"))
    )
    (net (code "135") (name "unconnected-(U4-6A-Pad14)") (class "Default")
      (node (ref "U4") (pin "14") (pinfunction "6A_14") (pintype "bidirectional"))
    )
    (net (code "136") (name "unconnected-(U4-6Y-Pad15)") (class "Default")
      (node (ref "U4") (pin "15") (pinfunction "6Y_15") (pintype "bidirectional"))
    )
    (net (code "137") (name "unconnected-(U5-N.C.-Pad4)") (class "Default")
      (node (ref "U5") (pin "4") (pinfunction "N.C._4") (pintype "no_connect"))
    )
    (net (code "138") (name "unconnected-(U5-~{CTS}-Pad11)") (class "Default")
      (node (ref "U5") (pin "11") (pinfunction "~{CTS}_11") (pintype "input"))
    )
    (net (code "139") (name "unconnected-(X3-Pad1)") (class "Default")
      (node (ref "X3") (pin "1") (pinfunction "1_1") (pintype "passive"))
    )
    (net (code "140") (name "unconnected-(X3-Pad4)") (class "Default")
      (node (ref "X3") (pin "4") (pinfunction "4_4") (pintype "passive"))
    )
    (net (code "141") (name "unconnected-(X3-Pad5)") (class "Default")
      (node (ref "X3") (pin "5") (pinfunction "5_5") (pintype "passive"))
    )
    (net (code "142") (name "unconnected-(X3-Pad6)") (class "Default")
      (node (ref "X3") (pin "6") (pinfunction "6_6") (pintype "passive"))
    )
    (net (code "143") (name "unconnected-(X3-Pad8)") (class "Default")
      (node (ref "X3") (pin "8") (pinfunction "8_8") (pintype "passive"))
    )
    (net (code "144") (name "unconnected-(X3-Pad9)") (class "Default")
      (node (ref "X3") (pin "9") (pinfunction "9_9") (pintype "passive"))
    )
    (net (code "145") (name "unconnected-(X4-COM_TERM-PadCOMMON)") (class "Default")
      (node (ref "X4") (pin "COMMON") (pinfunction "COM_TERM_COMMON") (pintype "input"))
    )
    (net (code "146") (name "unconnected-(X4-DETECT-PadCD)") (class "Default")
      (node (ref "X4") (pin "CD") (pinfunction "DETECT_CD") (pintype "input"))
    )
    (net (code "147") (name "unconnected-(X4-Pad8)") (class "Default")
      (node (ref "X4") (pin "8") (pinfunction "8_8") (pintype "input"))
    )
    (net (code "148") (name "unconnected-(X4-Pad9)") (class "Default")
      (node (ref "X4") (pin "9") (pinfunction "9_9") (pintype "input"))
    )
    (net (code "149") (name "unconnected-(X4-WRITE_PROT-PadWRITE_PROTECT)") (class "Default")
      (node (ref "X4") (pin "WRITE_PROTECT") (pinfunction "WRITE_PROT_WRITE_PROTECT") (pintype "input"))
    )
    (net (code "150") (name "unconnected-(X5-Pad1)") (class "Default")
      (node (ref "X5") (pin "1") (pinfunction "1_1") (pintype "passive"))
    )
    (net (code "151") (name "unconnected-(X5-Pad4)") (class "Default")
      (node (ref "X5") (pin "4") (pinfunction "4_4") (pintype "passive"))
    )
    (net (code "152") (name "unconnected-(X5-Pad5)") (class "Default")
      (node (ref "X5") (pin "5") (pinfunction "5_5") (pintype "passive"))
    )
    (net (code "153") (name "unconnected-(X5-Pad6)") (class "Default")
      (node (ref "X5") (pin "6") (pinfunction "6_6") (pintype "passive"))
    )
    (net (code "154") (name "unconnected-(X5-Pad8)") (class "Default")
      (node (ref "X5") (pin "8") (pinfunction "8_8") (pintype "passive"))
    )
    (net (code "155") (name "unconnected-(X5-Pad9)") (class "Default")
      (node (ref "X5") (pin "9") (pinfunction "9_9") (pintype "passive"))
    )
  )
)
